# SD_RAM.net
KiCad netlist of a schematic drawn in Altium Designer
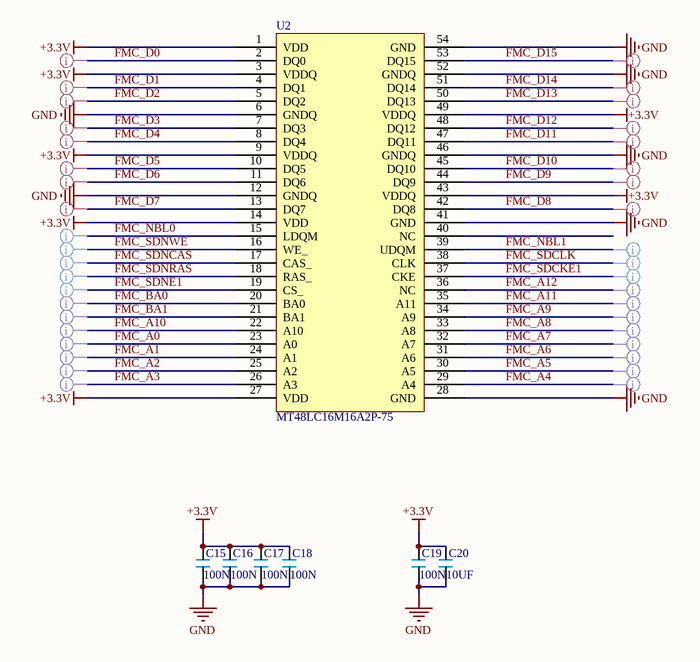
[diagram p0: SD_RAM.SchDoc]

(export (version "E")
  (design (tool "Eeschema 10.0.6"))
  (components
    (comp (ref "C15") (value "100N") (footprint "0603") (libsource (lib "R_L_C_V") (part "CAP")))
    (comp (ref "C16") (value "100N") (footprint "0603") (libsource (lib "R_L_C_V") (part "CAP")))
    (comp (ref "C17") (value "100N") (footprint "0603") (libsource (lib "R_L_C_V") (part "CAP")))
    (comp (ref "C18") (value "100N") (footprint "0603") (libsource (lib "R_L_C_V") (part "CAP")))
    (comp (ref "C19") (value "100N") (footprint "0603") (libsource (lib "R_L_C_V") (part "CAP")))
    (comp (ref "C20") (value "10UF") (footprint "0603") (libsource (lib "R_L_C_V") (part "CAP")))
    (comp (ref "U2")
      (value "MT48LC16M16A2P-75")
      (footprint "TSOP-54")
      (libsource (lib "MY_IC") (part "MT48LC16M16A2P-75"))
    )
  )
  (nets
    (net (code "1") (name "+3.3V") (class "Default")
      (node (ref "C15") (pin "2") (pintype "passive"))
      (node (ref "C16") (pin "2") (pintype "passive"))
      (node (ref "C17") (pin "2") (pintype "passive"))
      (node (ref "C18") (pin "2") (pintype "passive"))
      (node (ref "C19") (pin "2") (pintype "passive"))
      (node (ref "C20") (pin "2") (pintype "passive"))
      (node (ref "U2") (pin "1") (pinfunction "VDD_1") (pintype "passive"))
      (node (ref "U2") (pin "14") (pinfunction "VDD_14") (pintype "passive"))
      (node (ref "U2") (pin "27") (pinfunction "VDD_27") (pintype "passive"))
      (node (ref "U2") (pin "3") (pinfunction "VDDQ_3") (pintype "passive"))
      (node (ref "U2") (pin "43") (pinfunction "VDDQ_43") (pintype "passive"))
      (node (ref "U2") (pin "49") (pinfunction "VDDQ_49") (pintype "passive"))
      (node (ref "U2") (pin "9") (pinfunction "VDDQ_9") (pintype "passive"))
    )
    (net (code "2") (name "/FMC_A0") (class "Default")
      (node (ref "U2") (pin "23") (pinfunction "A0_23") (pintype "passive"))
    )
    (net (code "3") (name "/FMC_A1") (class "Default")
      (node (ref "U2") (pin "24") (pinfunction "A1_24") (pintype "passive"))
    )
    (net (code "4") (name "/FMC_A2") (class "Default")
      (node (ref "U2") (pin "25") (pinfunction "A2_25") (pintype "passive"))
    )
    (net (code "5") (name "/FMC_A3") (class "Default")
      (node (ref "U2") (pin "26") (pinfunction "A3_26") (pintype "passive"))
    )
    (net (code "6") (name "/FMC_A4") (class "Default")
      (node (ref "U2") (pin "29") (pinfunction "A4_29") (pintype "passive"))
    )
    (net (code "7") (name "/FMC_A5") (class "Default")
      (node (ref "U2") (pin "30") (pinfunction "A5_30") (pintype "passive"))
    )
    (net (code "8") (name "/FMC_A6") (class "Default")
      (node (ref "U2") (pin "31") (pinfunction "A6_31") (pintype "passive"))
    )
    (net (code "9") (name "/FMC_A7") (class "Default")
      (node (ref "U2") (pin "32") (pinfunction "A7_32") (pintype "passive"))
    )
    (net (code "10") (name "/FMC_A8") (class "Default")
      (node (ref "U2") (pin "33") (pinfunction "A8_33") (pintype "passive"))
    )
    (net (code "11") (name "/FMC_A9") (class "Default")
      (node (ref "U2") (pin "34") (pinfunction "A9_34") (pintype "passive"))
    )
    (net (code "12") (name "/FMC_A10") (class "Default")
      (node (ref "U2") (pin "22") (pinfunction "A10_22") (pintype "passive"))
    )
    (net (code "13") (name "/FMC_A11") (class "Default")
      (node (ref "U2") (pin "35") (pinfunction "A11_35") (pintype "passive"))
    )
    (net (code "14") (name "/FMC_A12") (class "Default")
      (node (ref "U2") (pin "36") (pinfunction "NC_36") (pintype "passive"))
    )
    (net (code "15") (name "/FMC_BA0") (class "Default")
      (node (ref "U2") (pin "20") (pinfunction "BA0_20") (pintype "passive"))
    )
    (net (code "16") (name "/FMC_BA1") (class "Default")
      (node (ref "U2") (pin "21") (pinfunction "BA1_21") (pintype "passive"))
    )
    (net (code "17") (name "/FMC_D0") (class "Default")
      (node (ref "U2") (pin "2") (pinfunction "DQ0_2") (pintype "passive"))
    )
    (net (code "18") (name "/FMC_D1") (class "Default")
      (node (ref "U2") (pin "4") (pinfunction "DQ1_4") (pintype "passive"))
    )
    (net (code "19") (name "/FMC_D2") (class "Default")
      (node (ref "U2") (pin "5") (pinfunction "DQ2_5") (pintype "passive"))
    )
    (net (code "20") (name "/FMC_D3") (class "Default")
      (node (ref "U2") (pin "7") (pinfunction "DQ3_7") (pintype "passive"))
    )
    (net (code "21") (name "/FMC_D4") (class "Default")
      (node (ref "U2") (pin "8") (pinfunction "DQ4_8") (pintype "passive"))
    )
    (net (code "22") (name "/FMC_D5") (class "Default")
      (node (ref "U2") (pin "10") (pinfunction "DQ5_10") (pintype "passive"))
    )
    (net (code "23") (name "/FMC_D6") (class "Default")
      (node (ref "U2") (pin "11") (pinfunction "DQ6_11") (pintype "passive"))
    )
    (net (code "24") (name "/FMC_D7") (class "Default")
      (node (ref "U2") (pin "13") (pinfunction "DQ7_13") (pintype "passive"))
    )
    (net (code "25") (name "/FMC_D8") (class "Default")
      (node (ref "U2") (pin "42") (pinfunction "DQ8_42") (pintype "passive"))
    )
    (net (code "26") (name "/FMC_D9") (class "Default")
      (node (ref "U2") (pin "44") (pinfunction "DQ9_44") (pintype "passive"))
    )
    (net (code "27") (name "/FMC_D10") (class "Default")
      (node (ref "U2") (pin "45") (pinfunction "DQ10_45") (pintype "passive"))
    )
    (net (code "28") (name "/FMC_D11") (class "Default")
      (node (ref "U2") (pin "47") (pinfunction "DQ11_47") (pintype "passive"))
    )
    (net (code "29") (name "/FMC_D12") (class "Default")
      (node (ref "U2") (pin "48") (pinfunction "DQ12_48") (pintype "passive"))
    )
    (net (code "30") (name "/FMC_D13") (class "Default")
      (node (ref "U2") (pin "50") (pinfunction "DQ13_50") (pintype "passive"))
    )
    (net (code "31") (name "/FMC_D14") (class "Default")
      (node (ref "U2") (pin "51") (pinfunction "DQ14_51") (pintype "passive"))
    )
    (net (code "32") (name "/FMC_D15") (class "Default")
      (node (ref "U2") (pin "53") (pinfunction "DQ15_53") (pintype "passive"))
    )
    (net (code "33") (name "/FMC_NBL0") (class "Default")
      (node (ref "U2") (pin "15") (pinfunction "LDQM_15") (pintype "passive"))
    )
    (net (code "34") (name "/FMC_NBL1") (class "Default")
      (node (ref "U2") (pin "39") (pinfunction "UDQM_39") (pintype "passive"))
    )
    (net (code "35") (name "/FMC_SDCKE1") (class "Default")
      (node (ref "U2") (pin "37") (pinfunction "CKE_37") (pintype "passive"))
    )
    (net (code "36") (name "/FMC_SDCLK") (class "Default")
      (node (ref "U2") (pin "38") (pinfunction "CLK_38") (pintype "passive"))
    )
    (net (code "37") (name "/FMC_SDNCAS") (class "Default")
      (node (ref "U2") (pin "17") (pinfunction "CAS__17") (pintype "passive"))
    )
    (net (code "38") (name "/FMC_SDNE1") (class "Default")
      (node (ref "U2") (pin "19") (pinfunction "CS__19") (pintype "passive"))
    )
    (net (code "39") (name "/FMC_SDNRAS") (class "Default")
      (node (ref "U2") (pin "18") (pinfunction "RAS__18") (pintype "passive"))
    )
    (net (code "40") (name "/FMC_SDNWE") (class "Default")
      (node (ref "U2") (pin "16") (pinfunction "WE__16") (pintype "passive"))
    )
    (net (code "41") (name "GND") (class "Default")
      (node (ref "C15") (pin "1") (pintype "passive"))
      (node (ref "C16") (pin "1") (pintype "passive"))
      (node (ref "C17") (pin "1") (pintype "passive"))
      (node (ref "C18") (pin "1") (pintype "passive"))
      (node (ref "C19") (pin "1") (pintype "passive"))
      (node (ref "C20") (pin "1") (pintype "passive"))
      (node (ref "U2") (pin "12") (pinfunction "GNDQ_12") (pintype "passive"))
      (node (ref "U2") (pin "28") (pinfunction "GND_28") (pintype "passive"))
      (node (ref "U2") (pin "41") (pinfunction "GND_41") (pintype "passive"))
      (node (ref "U2") (pin "46") (pinfunction "GNDQ_46") (pintype "passive"))
      (node (ref "U2") (pin "52") (pinfunction "GNDQ_52") (pintype "passive"))
      (node (ref "U2") (pin "54") (pinfunction "GND_54") (pintype "passive"))
      (node (ref "U2") (pin "6") (pinfunction "GNDQ_6") (pintype "passive"))
    )
    (net (code "42") (name "unconnected-(U2-NC-Pad40)") (class "Default")
      (node (ref "U2") (pin "40") (pinfunction "NC_40") (pintype "passive"))
    )
  )
)
